# Main.net
KiCad netlist of a schematic drawn in Altium Designer
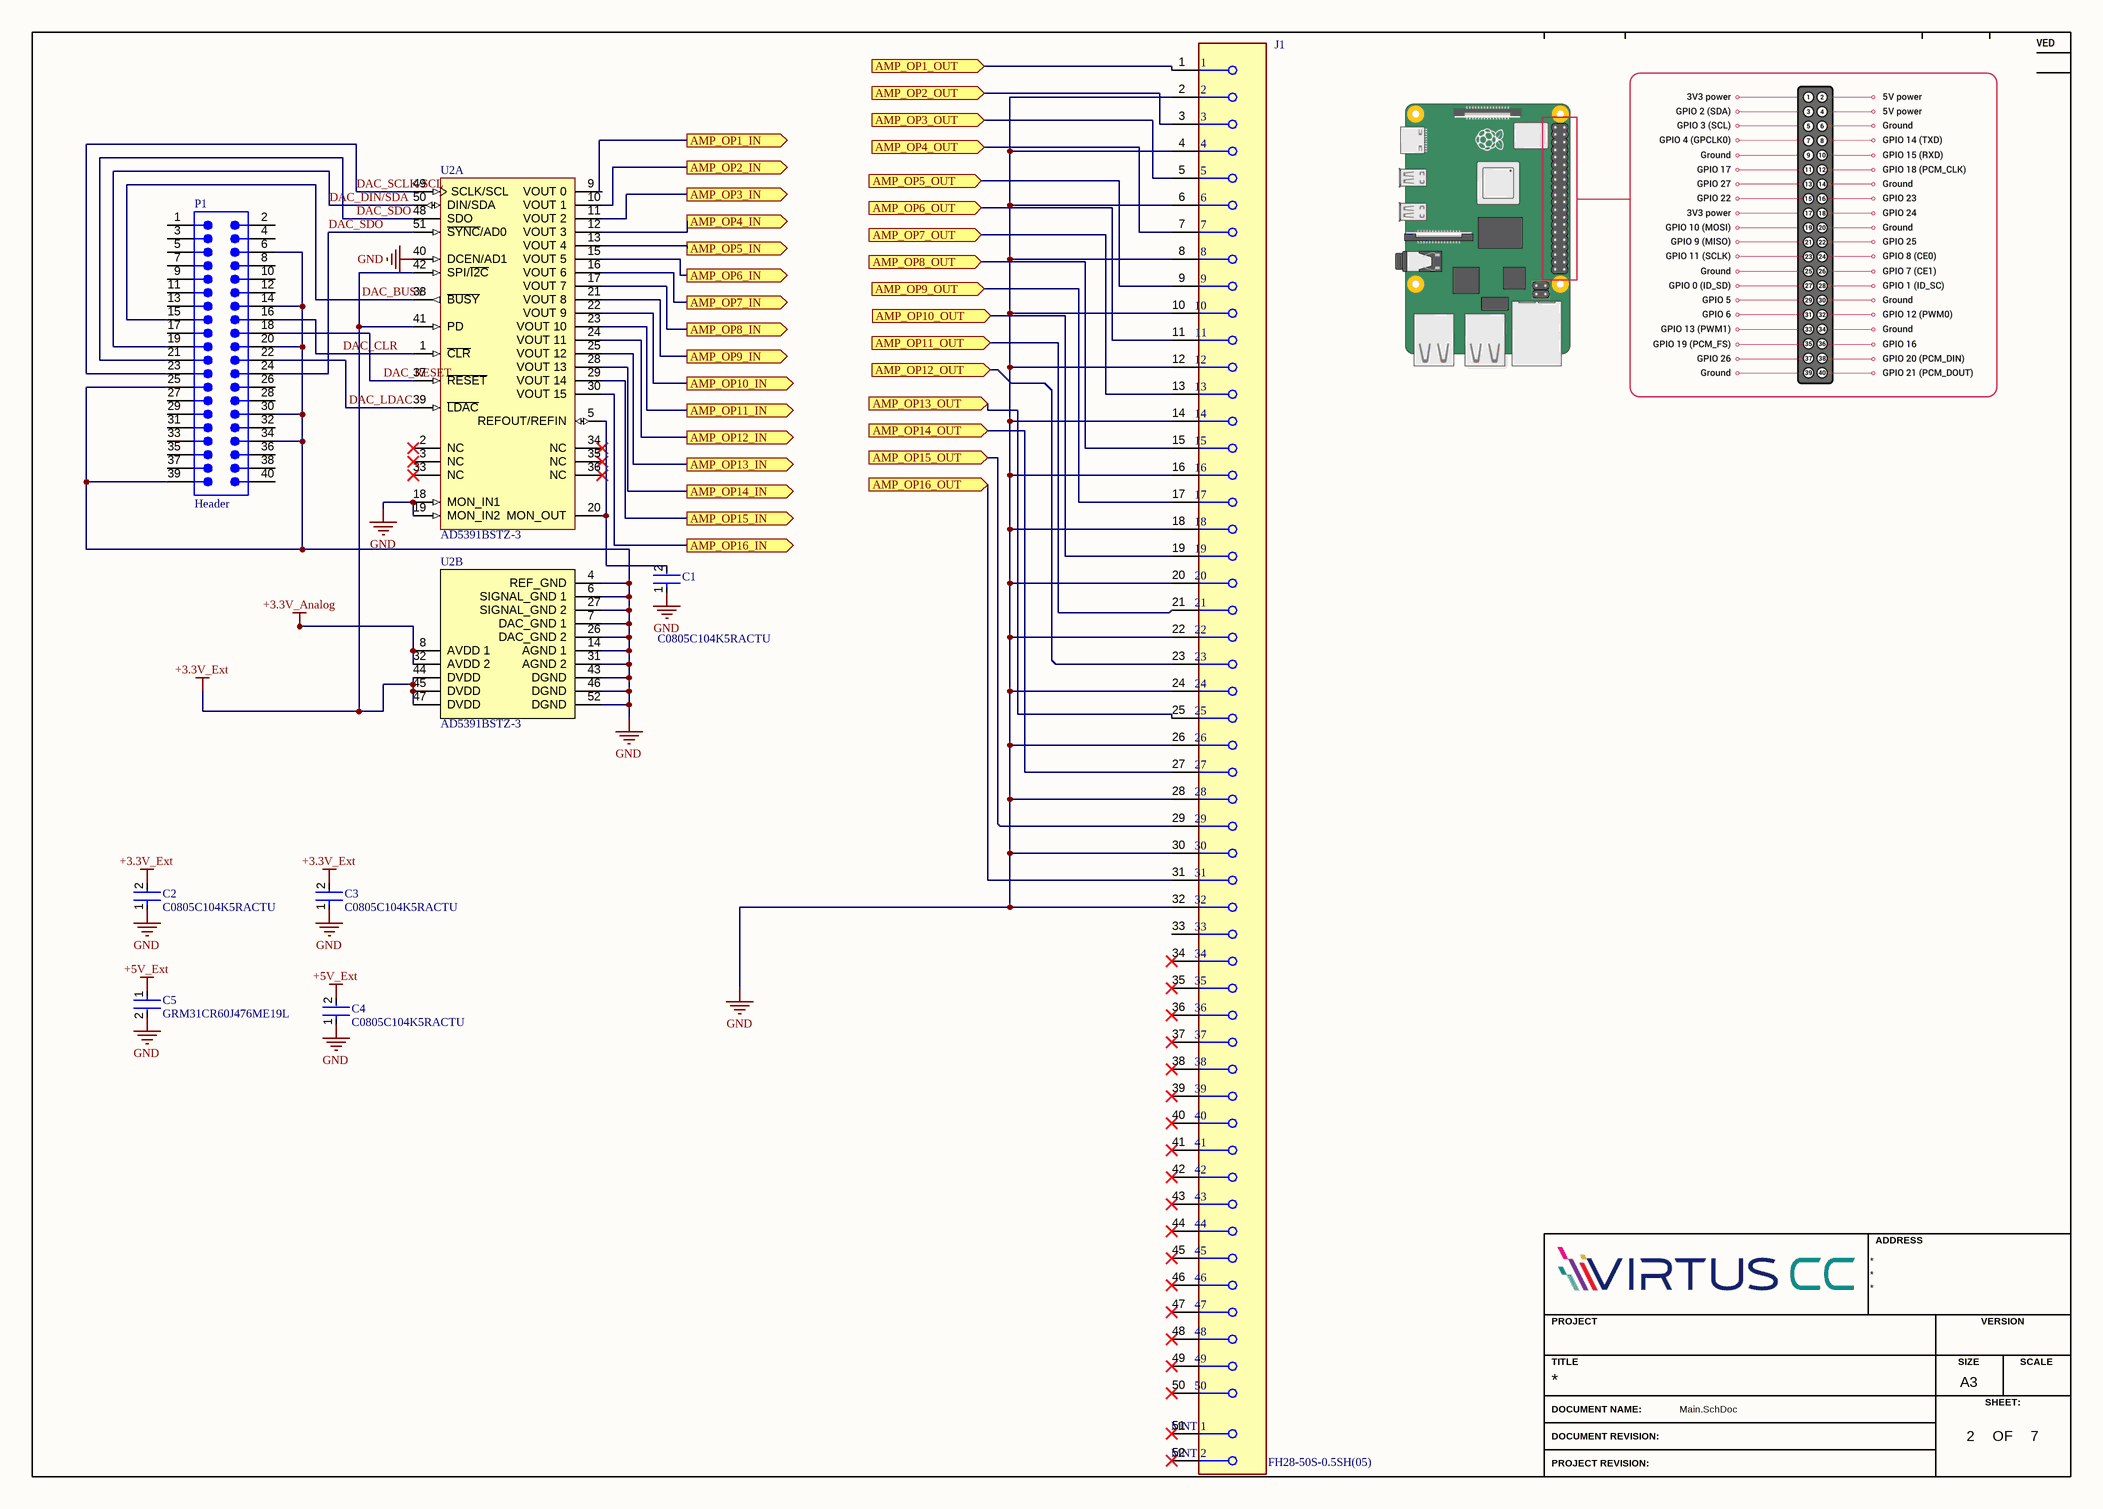
[diagram p0: Main.SchDoc]

(export (version "E")
  (design (tool "Eeschema 10.0.6"))
  (components
    (comp (ref "C1")
      (value "C0805C104K5RACTU")
      (footprint "FP-C0805C-DN-MFG")
      (description "CAP CER 0.1UF 50V X7R 0805")
      (fields
        (field (name "MANUFACTURER") "KEMET")
        (field (name "OCTOPART") "https://octopart.com/c0805c104k5ractu-kemet-143926")
      )
      (libsource (lib "Altium Content Vault") (part "b4654b650e69147ec39a6b967a45e02"))
    )
    (comp (ref "C2")
      (value "C0805C104K5RACTU")
      (footprint "FP-C0805C-DN-MFG")
      (description "CAP CER 0.1UF 50V X7R 0805")
      (fields
        (field (name "MANUFACTURER") "KEMET")
        (field (name "OCTOPART") "https://octopart.com/c0805c104k5ractu-kemet-143926")
      )
      (libsource (lib "Altium Content Vault") (part "b4654b650e69147ec39a6b967a45e02"))
    )
    (comp (ref "C3")
      (value "C0805C104K5RACTU")
      (footprint "FP-C0805C-DN-MFG")
      (description "CAP CER 0.1UF 50V X7R 0805")
      (fields
        (field (name "MANUFACTURER") "KEMET")
        (field (name "OCTOPART") "https://octopart.com/c0805c104k5ractu-kemet-143926")
      )
      (libsource (lib "Altium Content Vault") (part "b4654b650e69147ec39a6b967a45e02"))
    )
    (comp (ref "C4")
      (value "C0805C104K5RACTU")
      (footprint "FP-C0805C-DN-MFG")
      (description "CAP CER 0.1UF 50V X7R 0805")
      (fields
        (field (name "MANUFACTURER") "KEMET")
        (field (name "OCTOPART") "https://octopart.com/c0805c104k5ractu-kemet-143926")
      )
      (libsource (lib "Altium Content Vault") (part "b4654b650e69147ec39a6b967a45e02"))
    )
    (comp (ref "C5")
      (value "GRM31CR60J476ME19L")
      (footprint "FP-GRM31C-0_2-e0_3_0_8-IPC_C")
      (description "Chip Multilayer Ceramic Capacitors for General Purpose, 1206, 47uF, X5R, 15%, 20%, 6.3V")
      (fields (field (name "TOLERANCE") "20%") (field (name "VOLTAGE") "6.3V"))
      (libsource (lib "Altium Content Vault") (part "02cd4be3c70576c341d710602a673aa"))
    )
    (comp (ref "J1")
      (value "FH28-50S-0.5SH(05)")
      (footprint "FP-FH28-50S-0_5SH_05-MFG")
      (description "CONN FFC BOTTOM 50POS 0.50MM R/A")
      (fields
        (field (name "OCTOPART") "https://octopart.com/fh28-50s-0.5sh%2805%29-hirose-240232")
        (field (name "MANUFACTURER") "Hirose Electric Co Ltd")
      )
      (libsource (lib "Altium Content Vault") (part "b58b7e437d2d31add36c43a93be18f6"))
    )
    (comp (ref "P1")
      (value "Header")
      (footprint "61204021621")
      (description "WR-BHD Straight Male, Box Header, Through Hole, 2 Rows, 40 Contacts, 2.54mm Pitch")
      (libsource (lib "Altium Content Vault") (part "Header_Male_2R_40P"))
    )
    (comp (ref "U2")
      (value "AD5391BSTZ-3")
      (footprint "ST-52_L")
      (fields (field (name "MANUFACTURER") "Analog Devices") (field (name "GENERIC PART NUMBER") "AD5391"))
      (libsource (lib "Altium Content Vault") (part "ADI-AD5391-ST-52"))
    )
  )
  (nets
    (net (code "1") (name "+3.3V_Analog") (class "Default")
      (node (ref "U2") (pin "32") (pinfunction "AVDD_2_32") (pintype "power_in"))
      (node (ref "U2") (pin "8") (pinfunction "AVDD_1_8") (pintype "power_in"))
    )
    (net (code "2") (name "+3.3V_Ext") (class "Default")
      (node (ref "C2") (pin "2") (pinfunction "2_2") (pintype "passive"))
      (node (ref "C3") (pin "2") (pinfunction "2_2") (pintype "passive"))
      (node (ref "U2") (pin "41") (pinfunction "PD_41") (pintype "input"))
      (node (ref "U2") (pin "42") (pinfunction "SPI/~{I2C}_42") (pintype "input"))
      (node (ref "U2") (pin "44") (pinfunction "DVDD_44") (pintype "power_in"))
      (node (ref "U2") (pin "45") (pinfunction "DVDD_45") (pintype "power_in"))
      (node (ref "U2") (pin "47") (pinfunction "DVDD_47") (pintype "power_in"))
    )
    (net (code "3") (name "+5V_Ext") (class "Default")
      (node (ref "C4") (pin "2") (pinfunction "2_2") (pintype "passive"))
      (node (ref "C5") (pin "1") (pinfunction "1_1") (pintype "passive"))
    )
    (net (code "4") (name "/AMP_OP1_IN") (class "Default")
      (node (ref "U2") (pin "9") (pinfunction "VOUT_0_9") (pintype "tri_state"))
    )
    (net (code "5") (name "/AMP_OP1_OUT") (class "Default")
      (node (ref "J1") (pin "1") (pinfunction "1_1") (pintype "passive"))
    )
    (net (code "6") (name "/AMP_OP2_IN") (class "Default")
      (node (ref "U2") (pin "10") (pinfunction "VOUT_1_10") (pintype "tri_state"))
    )
    (net (code "7") (name "/AMP_OP2_OUT") (class "Default")
      (node (ref "J1") (pin "3") (pinfunction "3_3") (pintype "passive"))
    )
    (net (code "8") (name "/AMP_OP3_IN") (class "Default")
      (node (ref "U2") (pin "11") (pinfunction "VOUT_2_11") (pintype "tri_state"))
    )
    (net (code "9") (name "/AMP_OP3_OUT") (class "Default")
      (node (ref "J1") (pin "5") (pinfunction "5_5") (pintype "passive"))
    )
    (net (code "10") (name "/AMP_OP4_IN") (class "Default")
      (node (ref "U2") (pin "12") (pinfunction "VOUT_3_12") (pintype "tri_state"))
    )
    (net (code "11") (name "/AMP_OP4_OUT") (class "Default")
      (node (ref "J1") (pin "7") (pinfunction "7_7") (pintype "passive"))
    )
    (net (code "12") (name "/AMP_OP5_IN") (class "Default")
      (node (ref "U2") (pin "13") (pinfunction "VOUT_4_13") (pintype "tri_state"))
    )
    (net (code "13") (name "/AMP_OP5_OUT") (class "Default")
      (node (ref "J1") (pin "9") (pinfunction "9_9") (pintype "passive"))
    )
    (net (code "14") (name "/AMP_OP6_IN") (class "Default")
      (node (ref "U2") (pin "15") (pinfunction "VOUT_5_15") (pintype "tri_state"))
    )
    (net (code "15") (name "/AMP_OP6_OUT") (class "Default")
      (node (ref "J1") (pin "11") (pinfunction "11_11") (pintype "passive"))
    )
    (net (code "16") (name "/AMP_OP7_IN") (class "Default")
      (node (ref "U2") (pin "16") (pinfunction "VOUT_6_16") (pintype "tri_state"))
    )
    (net (code "17") (name "/AMP_OP7_OUT") (class "Default")
      (node (ref "J1") (pin "13") (pinfunction "13_13") (pintype "passive"))
    )
    (net (code "18") (name "/AMP_OP8_IN") (class "Default")
      (node (ref "U2") (pin "17") (pinfunction "VOUT_7_17") (pintype "tri_state"))
    )
    (net (code "19") (name "/AMP_OP8_OUT") (class "Default")
      (node (ref "J1") (pin "15") (pinfunction "15_15") (pintype "passive"))
    )
    (net (code "20") (name "/AMP_OP9_IN") (class "Default")
      (node (ref "U2") (pin "21") (pinfunction "VOUT_8_21") (pintype "tri_state"))
    )
    (net (code "21") (name "/AMP_OP9_OUT") (class "Default")
      (node (ref "J1") (pin "17") (pinfunction "17_17") (pintype "passive"))
    )
    (net (code "22") (name "/AMP_OP10_IN") (class "Default")
      (node (ref "U2") (pin "22") (pinfunction "VOUT_9_22") (pintype "tri_state"))
    )
    (net (code "23") (name "/AMP_OP10_OUT") (class "Default")
      (node (ref "J1") (pin "19") (pinfunction "19_19") (pintype "passive"))
    )
    (net (code "24") (name "/AMP_OP11_IN") (class "Default")
      (node (ref "U2") (pin "23") (pinfunction "VOUT_10_23") (pintype "tri_state"))
    )
    (net (code "25") (name "/AMP_OP11_OUT") (class "Default")
      (node (ref "J1") (pin "21") (pinfunction "21_21") (pintype "passive"))
    )
    (net (code "26") (name "/AMP_OP12_IN") (class "Default")
      (node (ref "U2") (pin "24") (pinfunction "VOUT_11_24") (pintype "tri_state"))
    )
    (net (code "27") (name "/AMP_OP12_OUT") (class "Default")
      (node (ref "J1") (pin "23") (pinfunction "23_23") (pintype "passive"))
    )
    (net (code "28") (name "/AMP_OP13_IN") (class "Default")
      (node (ref "U2") (pin "25") (pinfunction "VOUT_12_25") (pintype "tri_state"))
    )
    (net (code "29") (name "/AMP_OP13_OUT") (class "Default")
      (node (ref "J1") (pin "25") (pinfunction "25_25") (pintype "passive"))
    )
    (net (code "30") (name "/AMP_OP14_IN") (class "Default")
      (node (ref "U2") (pin "28") (pinfunction "VOUT_13_28") (pintype "tri_state"))
    )
    (net (code "31") (name "/AMP_OP14_OUT") (class "Default")
      (node (ref "J1") (pin "27") (pinfunction "27_27") (pintype "passive"))
    )
    (net (code "32") (name "/AMP_OP15_IN") (class "Default")
      (node (ref "U2") (pin "29") (pinfunction "VOUT_14_29") (pintype "tri_state"))
    )
    (net (code "33") (name "/AMP_OP15_OUT") (class "Default")
      (node (ref "J1") (pin "29") (pinfunction "29_29") (pintype "passive"))
    )
    (net (code "34") (name "/AMP_OP16_IN") (class "Default")
      (node (ref "U2") (pin "30") (pinfunction "VOUT_15_30") (pintype "tri_state"))
    )
    (net (code "35") (name "/AMP_OP16_OUT") (class "Default")
      (node (ref "J1") (pin "31") (pinfunction "31_31") (pintype "passive"))
    )
    (net (code "36") (name "/DAC_BUSY") (class "Default")
      (node (ref "P1") (pin "15") (pinfunction "15_15") (pintype "passive"))
      (node (ref "U2") (pin "38") (pinfunction "~{BUSY}_38") (pintype "output"))
    )
    (net (code "37") (name "/DAC_CLR") (class "Default")
      (node (ref "P1") (pin "16") (pinfunction "16_16") (pintype "passive"))
      (node (ref "U2") (pin "1") (pinfunction "~{CLR}_1") (pintype "input"))
    )
    (net (code "38") (name "/DAC_DIN{slash}SDA") (class "Default")
      (node (ref "P1") (pin "19") (pinfunction "19_19") (pintype "passive"))
      (node (ref "U2") (pin "50") (pinfunction "DIN/SDA_50") (pintype "bidirectional"))
    )
    (net (code "39") (name "/DAC_LDAC") (class "Default")
      (node (ref "P1") (pin "22") (pinfunction "22_22") (pintype "passive"))
      (node (ref "U2") (pin "39") (pinfunction "~{LDAC}_39") (pintype "input"))
    )
    (net (code "40") (name "/DAC_RESET") (class "Default")
      (node (ref "P1") (pin "18") (pinfunction "18_18") (pintype "passive"))
      (node (ref "U2") (pin "37") (pinfunction "~{RESET}_37") (pintype "input"))
    )
    (net (code "41") (name "/DAC_SCLK{slash}SCL") (class "Default")
      (node (ref "P1") (pin "23") (pinfunction "23_23") (pintype "passive"))
      (node (ref "U2") (pin "49") (pinfunction "SCLK/SCL_49") (pintype "input"))
    )
    (net (code "42") (name "/DAC_SDO") (class "Default")
      (node (ref "P1") (pin "21") (pinfunction "21_21") (pintype "passive"))
      (node (ref "P1") (pin "24") (pinfunction "24_24") (pintype "passive"))
      (node (ref "U2") (pin "48") (pinfunction "SDO_48") (pintype "tri_state"))
      (node (ref "U2") (pin "51") (pinfunction "~{SYNC}/AD0_51") (pintype "input"))
    )
    (net (code "43") (name "GND") (class "Default")
      (node (ref "C1") (pin "1") (pinfunction "1_1") (pintype "passive"))
      (node (ref "C2") (pin "1") (pinfunction "1_1") (pintype "passive"))
      (node (ref "C3") (pin "1") (pinfunction "1_1") (pintype "passive"))
      (node (ref "C4") (pin "1") (pinfunction "1_1") (pintype "passive"))
      (node (ref "C5") (pin "2") (pinfunction "2_2") (pintype "passive"))
      (node (ref "J1") (pin "10") (pinfunction "10_10") (pintype "passive"))
      (node (ref "J1") (pin "12") (pinfunction "12_12") (pintype "passive"))
      (node (ref "J1") (pin "14") (pinfunction "14_14") (pintype "passive"))
      (node (ref "J1") (pin "16") (pinfunction "16_16") (pintype "passive"))
      (node (ref "J1") (pin "18") (pinfunction "18_18") (pintype "passive"))
      (node (ref "J1") (pin "2") (pinfunction "2_2") (pintype "passive"))
      (node (ref "J1") (pin "20") (pinfunction "20_20") (pintype "passive"))
      (node (ref "J1") (pin "22") (pinfunction "22_22") (pintype "passive"))
      (node (ref "J1") (pin "24") (pinfunction "24_24") (pintype "passive"))
      (node (ref "J1") (pin "26") (pinfunction "26_26") (pintype "passive"))
      (node (ref "J1") (pin "28") (pinfunction "28_28") (pintype "passive"))
      (node (ref "J1") (pin "30") (pinfunction "30_30") (pintype "passive"))
      (node (ref "J1") (pin "32") (pinfunction "32_32") (pintype "passive"))
      (node (ref "J1") (pin "4") (pinfunction "4_4") (pintype "passive"))
      (node (ref "J1") (pin "6") (pinfunction "6_6") (pintype "passive"))
      (node (ref "J1") (pin "8") (pinfunction "8_8") (pintype "passive"))
      (node (ref "P1") (pin "14") (pinfunction "14_14") (pintype "passive"))
      (node (ref "P1") (pin "20") (pinfunction "20_20") (pintype "passive"))
      (node (ref "P1") (pin "25") (pinfunction "25_25") (pintype "passive"))
      (node (ref "P1") (pin "30") (pinfunction "30_30") (pintype "passive"))
      (node (ref "P1") (pin "34") (pinfunction "34_34") (pintype "passive"))
      (node (ref "P1") (pin "39") (pinfunction "39_39") (pintype "passive"))
      (node (ref "P1") (pin "6") (pinfunction "6_6") (pintype "passive"))
      (node (ref "U2") (pin "14") (pinfunction "AGND_1_14") (pintype "power_in"))
      (node (ref "U2") (pin "18") (pinfunction "MON_IN1_18") (pintype "input"))
      (node (ref "U2") (pin "19") (pinfunction "MON_IN2_19") (pintype "input"))
      (node (ref "U2") (pin "26") (pinfunction "DAC_GND_2_26") (pintype "power_in"))
      (node (ref "U2") (pin "27") (pinfunction "SIGNAL_GND_2_27") (pintype "power_in"))
      (node (ref "U2") (pin "31") (pinfunction "AGND_2_31") (pintype "power_in"))
      (node (ref "U2") (pin "4") (pinfunction "REF_GND_4") (pintype "power_in"))
      (node (ref "U2") (pin "40") (pinfunction "DCEN/AD1_40") (pintype "input"))
      (node (ref "U2") (pin "43") (pinfunction "DGND_43") (pintype "power_in"))
      (node (ref "U2") (pin "46") (pinfunction "DGND_46") (pintype "power_in"))
      (node (ref "U2") (pin "52") (pinfunction "DGND_52") (pintype "power_in"))
      (node (ref "U2") (pin "6") (pinfunction "SIGNAL_GND_1_6") (pintype "power_in"))
      (node (ref "U2") (pin "7") (pinfunction "DAC_GND_1_7") (pintype "power_in"))
    )
    (net (code "44") (name "Net-(U2A-MON_OUT)") (class "Default")
      (node (ref "C1") (pin "2") (pinfunction "2_2") (pintype "passive"))
      (node (ref "U2") (pin "20") (pinfunction "MON_OUT_20") (pintype "tri_state"))
      (node (ref "U2") (pin "5") (pinfunction "REFOUT/REFIN_5") (pintype "bidirectional"))
    )
    (net (code "45") (name "unconnected-(J1-MNT_1-Pad51)") (class "Default")
      (node (ref "J1") (pin "51") (pinfunction "MNT_1_51") (pintype "passive+no_connect"))
    )
    (net (code "46") (name "unconnected-(J1-MNT_2-Pad52)") (class "Default")
      (node (ref "J1") (pin "52") (pinfunction "MNT_2_52") (pintype "passive+no_connect"))
    )
    (net (code "47") (name "unconnected-(J1-Pad33)") (class "Default")
      (node (ref "J1") (pin "33") (pinfunction "33_33") (pintype "passive"))
    )
    (net (code "48") (name "unconnected-(J1-Pad34)") (class "Default")
      (node (ref "J1") (pin "34") (pinfunction "34_34") (pintype "passive+no_connect"))
    )
    (net (code "49") (name "unconnected-(J1-Pad35)") (class "Default")
      (node (ref "J1") (pin "35") (pinfunction "35_35") (pintype "passive+no_connect"))
    )
    (net (code "50") (name "unconnected-(J1-Pad36)") (class "Default")
      (node (ref "J1") (pin "36") (pinfunction "36_36") (pintype "passive+no_connect"))
    )
    (net (code "51") (name "unconnected-(J1-Pad37)") (class "Default")
      (node (ref "J1") (pin "37") (pinfunction "37_37") (pintype "passive+no_connect"))
    )
    (net (code "52") (name "unconnected-(J1-Pad38)") (class "Default")
      (node (ref "J1") (pin "38") (pinfunction "38_38") (pintype "passive+no_connect"))
    )
    (net (code "53") (name "unconnected-(J1-Pad39)") (class "Default")
      (node (ref "J1") (pin "39") (pinfunction "39_39") (pintype "passive+no_connect"))
    )
    (net (code "54") (name "unconnected-(J1-Pad40)") (class "Default")
      (node (ref "J1") (pin "40") (pinfunction "40_40") (pintype "passive+no_connect"))
    )
    (net (code "55") (name "unconnected-(J1-Pad41)") (class "Default")
      (node (ref "J1") (pin "41") (pinfunction "41_41") (pintype "passive+no_connect"))
    )
    (net (code "56") (name "unconnected-(J1-Pad42)") (class "Default")
      (node (ref "J1") (pin "42") (pinfunction "42_42") (pintype "passive+no_connect"))
    )
    (net (code "57") (name "unconnected-(J1-Pad43)") (class "Default")
      (node (ref "J1") (pin "43") (pinfunction "43_43") (pintype "passive+no_connect"))
    )
    (net (code "58") (name "unconnected-(J1-Pad44)") (class "Default")
      (node (ref "J1") (pin "44") (pinfunction "44_44") (pintype "passive+no_connect"))
    )
    (net (code "59") (name "unconnected-(J1-Pad45)") (class "Default")
      (node (ref "J1") (pin "45") (pinfunction "45_45") (pintype "passive+no_connect"))
    )
    (net (code "60") (name "unconnected-(J1-Pad46)") (class "Default")
      (node (ref "J1") (pin "46") (pinfunction "46_46") (pintype "passive+no_connect"))
    )
    (net (code "61") (name "unconnected-(J1-Pad47)") (class "Default")
      (node (ref "J1") (pin "47") (pinfunction "47_47") (pintype "passive+no_connect"))
    )
    (net (code "62") (name "unconnected-(J1-Pad48)") (class "Default")
      (node (ref "J1") (pin "48") (pinfunction "48_48") (pintype "passive+no_connect"))
    )
    (net (code "63") (name "unconnected-(J1-Pad49)") (class "Default")
      (node (ref "J1") (pin "49") (pinfunction "49_49") (pintype "passive+no_connect"))
    )
    (net (code "64") (name "unconnected-(J1-Pad50)") (class "Default")
      (node (ref "J1") (pin "50") (pinfunction "50_50") (pintype "passive+no_connect"))
    )
    (net (code "65") (name "unconnected-(P1-Pad1)") (class "Default")
      (node (ref "P1") (pin "1") (pinfunction "1_1") (pintype "passive"))
    )
    (net (code "66") (name "unconnected-(P1-Pad2)") (class "Default")
      (node (ref "P1") (pin "2") (pinfunction "2_2") (pintype "passive"))
    )
    (net (code "67") (name "unconnected-(P1-Pad3)") (class "Default")
      (node (ref "P1") (pin "3") (pinfunction "3_3") (pintype "passive"))
    )
    (net (code "68") (name "unconnected-(P1-Pad4)") (class "Default")
      (node (ref "P1") (pin "4") (pinfunction "4_4") (pintype "passive"))
    )
    (net (code "69") (name "unconnected-(P1-Pad5)") (class "Default")
      (node (ref "P1") (pin "5") (pinfunction "5_5") (pintype "passive"))
    )
    (net (code "70") (name "unconnected-(P1-Pad7)") (class "Default")
      (node (ref "P1") (pin "7") (pinfunction "7_7") (pintype "passive"))
    )
    (net (code "71") (name "unconnected-(P1-Pad8)") (class "Default")
      (node (ref "P1") (pin "8") (pinfunction "8_8") (pintype "passive"))
    )
    (net (code "72") (name "unconnected-(P1-Pad9)") (class "Default")
      (node (ref "P1") (pin "9") (pinfunction "9_9") (pintype "passive"))
    )
    (net (code "73") (name "unconnected-(P1-Pad10)") (class "Default")
      (node (ref "P1") (pin "10") (pinfunction "10_10") (pintype "passive"))
    )
    (net (code "74") (name "unconnected-(P1-Pad11)") (class "Default")
      (node (ref "P1") (pin "11") (pinfunction "11_11") (pintype "passive"))
    )
    (net (code "75") (name "unconnected-(P1-Pad12)") (class "Default")
      (node (ref "P1") (pin "12") (pinfunction "12_12") (pintype "passive"))
    )
    (net (code "76") (name "unconnected-(P1-Pad13)") (class "Default")
      (node (ref "P1") (pin "13") (pinfunction "13_13") (pintype "passive"))
    )
    (net (code "77") (name "unconnected-(P1-Pad17)") (class "Default")
      (node (ref "P1") (pin "17") (pinfunction "17_17") (pintype "passive"))
    )
    (net (code "78") (name "unconnected-(P1-Pad26)") (class "Default")
      (node (ref "P1") (pin "26") (pinfunction "26_26") (pintype "passive"))
    )
    (net (code "79") (name "unconnected-(P1-Pad27)") (class "Default")
      (node (ref "P1") (pin "27") (pinfunction "27_27") (pintype "passive"))
    )
    (net (code "80") (name "unconnected-(P1-Pad28)") (class "Default")
      (node (ref "P1") (pin "28") (pinfunction "28_28") (pintype "passive"))
    )
    (net (code "81") (name "unconnected-(P1-Pad29)") (class "Default")
      (node (ref "P1") (pin "29") (pinfunction "29_29") (pintype "passive"))
    )
    (net (code "82") (name "unconnected-(P1-Pad31)") (class "Default")
      (node (ref "P1") (pin "31") (pinfunction "31_31") (pintype "passive"))
    )
    (net (code "83") (name "unconnected-(P1-Pad32)") (class "Default")
      (node (ref "P1") (pin "32") (pinfunction "32_32") (pintype "passive"))
    )
    (net (code "84") (name "unconnected-(P1-Pad33)") (class "Default")
      (node (ref "P1") (pin "33") (pinfunction "33_33") (pintype "passive"))
    )
    (net (code "85") (name "unconnected-(P1-Pad35)") (class "Default")
      (node (ref "P1") (pin "35") (pinfunction "35_35") (pintype "passive"))
    )
    (net (code "86") (name "unconnected-(P1-Pad36)") (class "Default")
      (node (ref "P1") (pin "36") (pinfunction "36_36") (pintype "passive"))
    )
    (net (code "87") (name "unconnected-(P1-Pad37)") (class "Default")
      (node (ref "P1") (pin "37") (pinfunction "37_37") (pintype "passive"))
    )
    (net (code "88") (name "unconnected-(P1-Pad38)") (class "Default")
      (node (ref "P1") (pin "38") (pinfunction "38_38") (pintype "passive"))
    )
    (net (code "89") (name "unconnected-(P1-Pad40)") (class "Default")
      (node (ref "P1") (pin "40") (pinfunction "40_40") (pintype "passive"))
    )
    (net (code "90") (name "unconnected-(U2A-NC-Pad2)") (class "Default")
      (node (ref "U2") (pin "2") (pinfunction "NC_2") (pintype "passive+no_connect"))
    )
    (net (code "91") (name "unconnected-(U2A-NC-Pad3)") (class "Default")
      (node (ref "U2") (pin "3") (pinfunction "NC_3") (pintype "passive+no_connect"))
    )
    (net (code "92") (name "unconnected-(U2A-NC-Pad33)") (class "Default")
      (node (ref "U2") (pin "33") (pinfunction "NC_33") (pintype "passive+no_connect"))
    )
    (net (code "93") (name "unconnected-(U2A-NC-Pad34)") (class "Default")
      (node (ref "U2") (pin "34") (pinfunction "NC_34") (pintype "passive+no_connect"))
    )
    (net (code "94") (name "unconnected-(U2A-NC-Pad35)") (class "Default")
      (node (ref "U2") (pin "35") (pinfunction "NC_35") (pintype "passive+no_connect"))
    )
    (net (code "95") (name "unconnected-(U2A-NC-Pad36)") (class "Default")
      (node (ref "U2") (pin "36") (pinfunction "NC_36") (pintype "passive+no_connect"))
    )
  )
)
